# STM32F072B.net
KiCad netlist of a schematic drawn in Altium Designer
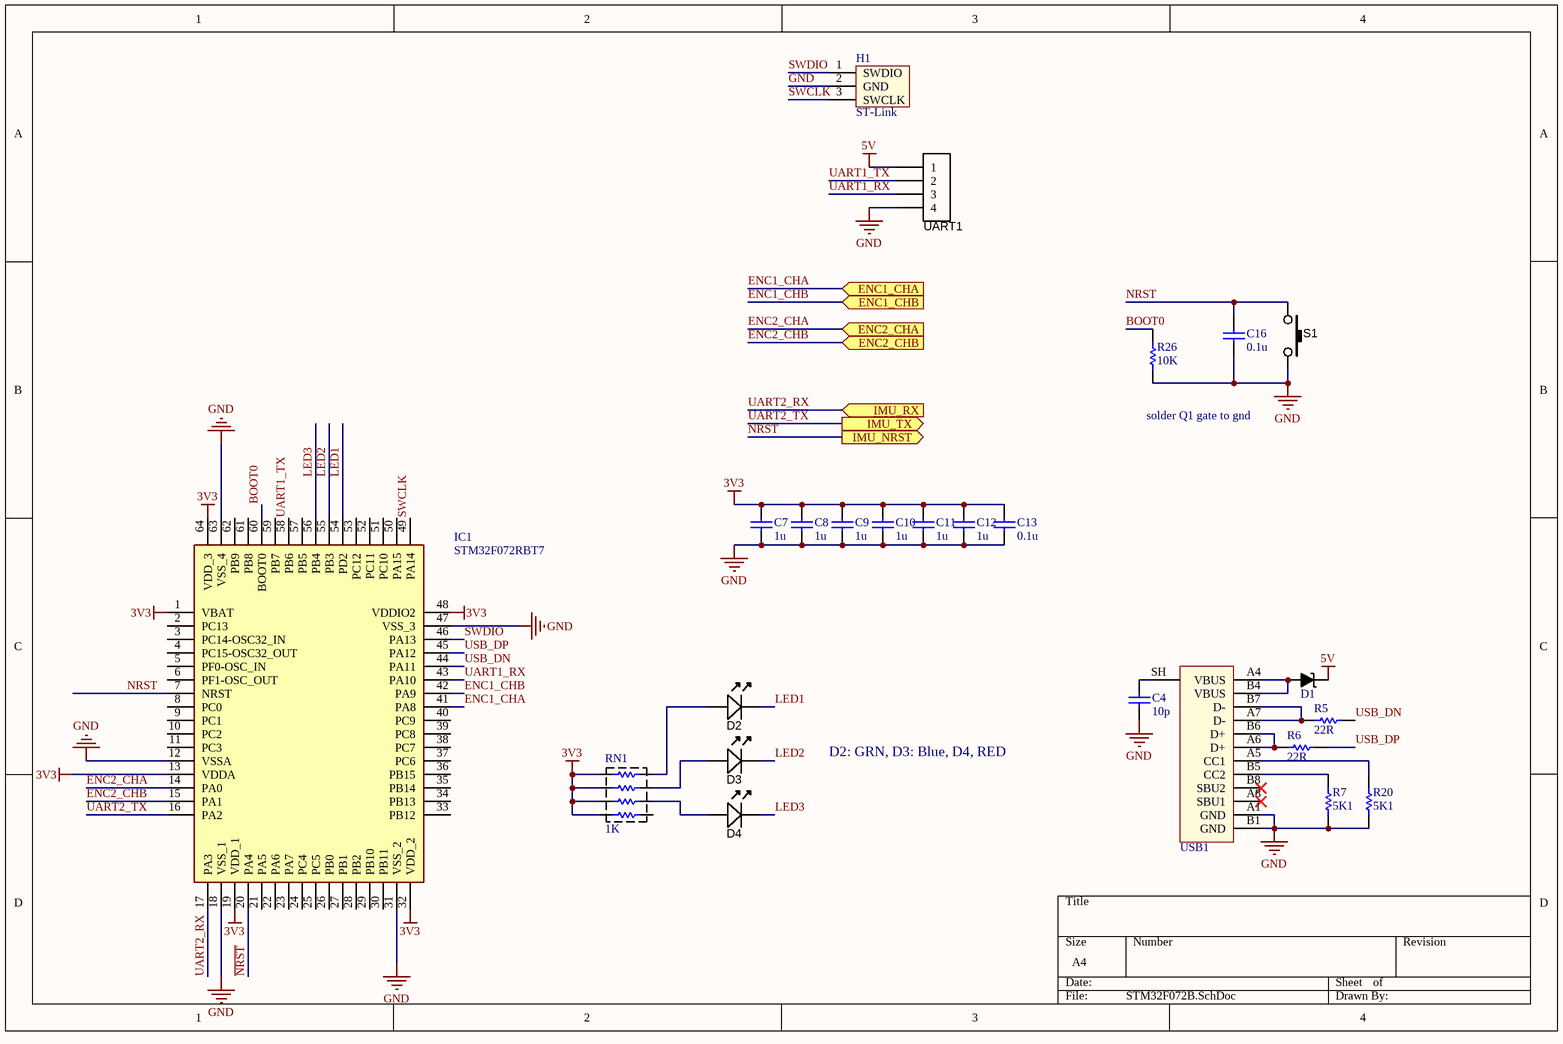
[diagram p0: STM32F072B.SchDoc]

(export (version "E")
  (design (tool "Eeschema 10.0.6"))
  (components
    (comp (ref "C4")
      (value "10p")
      (footprint "CAPC1608X90N")
      (description "Capacitor")
      (fields (field (name "Comment") "Cap") (field (name "PUBLISHER") "Altium Limited"))
      (libsource (lib "IOBoard_Low") (part "Cap"))
    )
    (comp (ref "C7")
      (value "1u")
      (footprint "CAPC1608X90N")
      (description "Capacitor")
      (fields (field (name "Comment") "Cap") (field (name "PUBLISHER") "Altium Limited"))
      (libsource (lib "IOBoard_Low") (part "Cap"))
    )
    (comp (ref "C8")
      (value "1u")
      (footprint "CAPC1608X90N")
      (description "Capacitor")
      (fields (field (name "Comment") "Cap") (field (name "PUBLISHER") "Altium Limited"))
      (libsource (lib "IOBoard_Low") (part "Cap"))
    )
    (comp (ref "C9")
      (value "1u")
      (footprint "CAPC1608X90N")
      (description "Capacitor")
      (fields (field (name "Comment") "Cap") (field (name "PUBLISHER") "Altium Limited"))
      (libsource (lib "IOBoard_Low") (part "Cap"))
    )
    (comp (ref "C10")
      (value "1u")
      (footprint "CAPC1608X90N")
      (description "Capacitor")
      (fields (field (name "Comment") "Cap") (field (name "PUBLISHER") "Altium Limited"))
      (libsource (lib "IOBoard_Low") (part "Cap"))
    )
    (comp (ref "C11")
      (value "1u")
      (footprint "CAPC1608X90N")
      (description "Capacitor")
      (fields (field (name "Comment") "Cap") (field (name "PUBLISHER") "Altium Limited"))
      (libsource (lib "IOBoard_Low") (part "Cap"))
    )
    (comp (ref "C12")
      (value "1u")
      (footprint "CAPC1608X90N")
      (description "Capacitor")
      (fields (field (name "Comment") "Cap") (field (name "PUBLISHER") "Altium Limited"))
      (libsource (lib "IOBoard_Low") (part "Cap"))
    )
    (comp (ref "C13")
      (value "0.1u")
      (footprint "CAPC1608X90N")
      (description "Capacitor")
      (fields (field (name "Comment") "Cap") (field (name "PUBLISHER") "Altium Limited"))
      (libsource (lib "IOBoard_Low") (part "Cap"))
    )
    (comp (ref "C16")
      (value "0.1u")
      (footprint "CAPC1608X90N")
      (description "Capacitor")
      (fields (field (name "Comment") "Cap") (field (name "PUBLISHER") "Altium Limited"))
      (libsource (lib "IOBoard_Low") (part "Cap"))
    )
    (comp (ref "D1")
      (value "diode")
      (footprint "DIODE_3216_70N")
      (description "40V 2A")
      (libsource (lib "IOBoard_Low") (part "SD1206S040S2R0"))
    )
    (comp (ref "D2")
      (value "LED_Green_GullWing")
      (footprint "LED-0805-A")
      (description "LED Gull-wing SMD High-intensity Green 450mcd 574nm")
      (libsource (lib "IOBoard") (part "LED_Green_GullWing"))
    )
    (comp (ref "D3")
      (value "LED_Green_GullWing")
      (footprint "LED-0805-A")
      (description "LED Gull-wing SMD High-intensity Green 450mcd 574nm")
      (libsource (lib "IOBoard") (part "LED_Green_GullWing"))
    )
    (comp (ref "D4")
      (value "LED_Green_GullWing")
      (footprint "LED-0805-A")
      (description "LED Gull-wing SMD High-intensity Green 450mcd 574nm")
      (libsource (lib "IOBoard") (part "LED_Green_GullWing"))
    )
    (comp (ref "H1")
      (value "ST-Link")
      (footprint "ST-Link")
      (description "ST-Link header with silkscreen")
      (libsource (lib "IOBoard") (part "ST-Link"))
    )
    (comp (ref "IC1")
      (value "STM32F072RBT7")
      (footprint "SamacSys:QFP50P1200X1200X160-64N")
      (description "Integrated Circuit")
      (fields (field (name "MOUSER PART NUMBER") "511-STM32F072RBT7"))
      (libsource (lib "*") (part "STM32F072RBT7"))
    )
    (comp (ref "R5")
      (value "22R")
      (footprint "RESC1608X55N")
      (description "Resistor")
      (fields (field (name "Comment") "Res1") (field (name "PUBLISHER") "Altium Limited"))
      (libsource (lib "IOBoard_Low") (part "Res1"))
    )
    (comp (ref "R6")
      (value "22R")
      (footprint "RESC1608X55N")
      (description "Resistor")
      (fields (field (name "Comment") "Res1") (field (name "PUBLISHER") "Altium Limited"))
      (libsource (lib "IOBoard_Low") (part "Res1"))
    )
    (comp (ref "R7")
      (value "5K1")
      (footprint "RESC1608X55N")
      (description "Resistor")
      (fields (field (name "Comment") "Res1") (field (name "PUBLISHER") "Altium Limited"))
      (libsource (lib "IOBoard_Low") (part "Res1"))
    )
    (comp (ref "R20")
      (value "5K1")
      (footprint "RESC1608X55N")
      (description "Resistor")
      (fields (field (name "Comment") "Res1") (field (name "PUBLISHER") "Altium Limited"))
      (libsource (lib "IOBoard_Low") (part "Res1"))
    )
    (comp (ref "R26")
      (value "10K")
      (footprint "RESC1608X55N")
      (description "Resistor")
      (fields (field (name "Comment") "Res1") (field (name "PUBLISHER") "Altium Limited"))
      (libsource (lib "IOBoard_Low") (part "Res1"))
    )
    (comp (ref "RN1")
      (value "1K")
      (footprint "RESCAXS50P160X320X70-8N")
      (fields (field (name "Comment") "resistor network"))
      (libsource (lib "IOBoard") (part "RES_NET"))
    )
    (comp (ref "S1")
      (value "SW_THT_PB_4.3mm")
      (footprint "TACT_SWT-SMD-4.4")
      (description "Switch, tact, 4.3mm stem")
      (libsource (lib "IOBoard") (part "SW_THT_PB_4.3mm"))
    )
    (comp (ref "UART1")
      (value "Programmer")
      (footprint "HDR1X4_2.54MMP")
      (description "Header 4-pin")
      (libsource (lib "IOBoard") (part "Header4P"))
    )
    (comp (ref "USB1")
      (value "USB type C connector")
      (footprint "TYPE-C-31-M-12")
      (libsource (lib "IOBoard") (part "USB_Type_C"))
    )
  )
  (nets
    (net (code "1") (name "/BOOT0") (class "Default")
      (node (ref "IC1") (pin "60") (pinfunction "BOOT0_60") (pintype "passive"))
      (node (ref "R26") (pin "2") (pinfunction "2_2") (pintype "passive"))
    )
    (net (code "2") (name "/ENC1_CHA") (class "Default")
      (node (ref "IC1") (pin "41") (pinfunction "PA8_41") (pintype "passive"))
    )
    (net (code "3") (name "/ENC1_CHB") (class "Default")
      (node (ref "IC1") (pin "42") (pinfunction "PA9_42") (pintype "passive"))
    )
    (net (code "4") (name "/ENC2_CHA") (class "Default")
      (node (ref "IC1") (pin "14") (pinfunction "PA0_14") (pintype "passive"))
    )
    (net (code "5") (name "/ENC2_CHB") (class "Default")
      (node (ref "IC1") (pin "15") (pinfunction "PA1_15") (pintype "passive"))
    )
    (net (code "6") (name "/LED1") (class "Default")
      (node (ref "D2") (pin "K") (pinfunction "K_K") (pintype "passive"))
      (node (ref "IC1") (pin "54") (pinfunction "PD2_54") (pintype "passive"))
    )
    (net (code "7") (name "/LED2") (class "Default")
      (node (ref "D3") (pin "K") (pinfunction "K_K") (pintype "passive"))
      (node (ref "IC1") (pin "55") (pinfunction "PB3_55") (pintype "passive"))
    )
    (net (code "8") (name "/LED3") (class "Default")
      (node (ref "D4") (pin "K") (pinfunction "K_K") (pintype "passive"))
      (node (ref "IC1") (pin "56") (pinfunction "PB4_56") (pintype "passive"))
    )
    (net (code "9") (name "/NRST") (class "Default")
      (node (ref "C16") (pin "2") (pinfunction "2_2") (pintype "passive"))
      (node (ref "IC1") (pin "7") (pinfunction "NRST_7") (pintype "passive"))
      (node (ref "S1") (pin "1") (pintype "passive"))
    )
    (net (code "10") (name "/SWCLK") (class "Default")
      (node (ref "H1") (pin "3") (pinfunction "SWCLK_3") (pintype "power_in"))
      (node (ref "IC1") (pin "49") (pinfunction "PA14_49") (pintype "passive"))
    )
    (net (code "11") (name "/SWDIO") (class "Default")
      (node (ref "H1") (pin "1") (pinfunction "SWDIO_1") (pintype "power_in"))
      (node (ref "IC1") (pin "46") (pinfunction "PA13_46") (pintype "passive"))
    )
    (net (code "12") (name "/UART1_RX") (class "Default")
      (node (ref "IC1") (pin "43") (pinfunction "PA10_43") (pintype "passive"))
      (node (ref "UART1") (pin "3") (pinfunction "3_3") (pintype "passive"))
    )
    (net (code "13") (name "/UART1_TX") (class "Default")
      (node (ref "IC1") (pin "58") (pinfunction "PB6_58") (pintype "passive"))
      (node (ref "UART1") (pin "2") (pinfunction "2_2") (pintype "passive"))
    )
    (net (code "14") (name "/UART2_RX") (class "Default")
      (node (ref "IC1") (pin "17") (pinfunction "PA3_17") (pintype "passive"))
    )
    (net (code "15") (name "/UART2_TX") (class "Default")
      (node (ref "IC1") (pin "16") (pinfunction "PA2_16") (pintype "passive"))
    )
    (net (code "16") (name "/USB_DN") (class "Default")
      (node (ref "IC1") (pin "44") (pinfunction "PA11_44") (pintype "passive"))
      (node (ref "R5") (pin "2") (pinfunction "2_2") (pintype "passive"))
    )
    (net (code "17") (name "/USB_DP") (class "Default")
      (node (ref "IC1") (pin "45") (pinfunction "PA12_45") (pintype "passive"))
      (node (ref "R6") (pin "2") (pinfunction "2_2") (pintype "passive"))
    )
    (net (code "18") (name "/~{NRST}") (class "Default")
      (node (ref "IC1") (pin "20") (pinfunction "PA4_20") (pintype "passive"))
    )
    (net (code "19") (name "3V3") (class "Default")
      (node (ref "C10") (pin "2") (pinfunction "2_2") (pintype "passive"))
      (node (ref "C11") (pin "2") (pinfunction "2_2") (pintype "passive"))
      (node (ref "C12") (pin "2") (pinfunction "2_2") (pintype "passive"))
      (node (ref "C13") (pin "2") (pinfunction "2_2") (pintype "passive"))
      (node (ref "C7") (pin "2") (pinfunction "2_2") (pintype "passive"))
      (node (ref "C8") (pin "2") (pinfunction "2_2") (pintype "passive"))
      (node (ref "C9") (pin "2") (pinfunction "2_2") (pintype "passive"))
      (node (ref "IC1") (pin "1") (pinfunction "VBAT_1") (pintype "passive"))
      (node (ref "IC1") (pin "13") (pinfunction "VDDA_13") (pintype "passive"))
      (node (ref "IC1") (pin "19") (pinfunction "VDD_1_19") (pintype "passive"))
      (node (ref "IC1") (pin "32") (pinfunction "VDD_2_32") (pintype "passive"))
      (node (ref "IC1") (pin "48") (pinfunction "VDDIO2_48") (pintype "passive"))
      (node (ref "IC1") (pin "64") (pinfunction "VDD_3_64") (pintype "passive"))
      (node (ref "RN1") (pin "1") (pinfunction "1_1") (pintype "power_in"))
      (node (ref "RN1") (pin "2") (pinfunction "2_2") (pintype "power_in"))
      (node (ref "RN1") (pin "3") (pinfunction "3_3") (pintype "power_in"))
      (node (ref "RN1") (pin "4") (pinfunction "4_4") (pintype "power_in"))
    )
    (net (code "20") (name "5V") (class "Default")
      (node (ref "D1") (pin "K") (pinfunction "Cathode_K") (pintype "passive"))
      (node (ref "UART1") (pin "1") (pinfunction "1_1") (pintype "passive"))
    )
    (net (code "21") (name "GND") (class "Default")
      (node (ref "C10") (pin "1") (pinfunction "1_1") (pintype "passive"))
      (node (ref "C11") (pin "1") (pinfunction "1_1") (pintype "passive"))
      (node (ref "C12") (pin "1") (pinfunction "1_1") (pintype "passive"))
      (node (ref "C13") (pin "1") (pinfunction "1_1") (pintype "passive"))
      (node (ref "C16") (pin "1") (pinfunction "1_1") (pintype "passive"))
      (node (ref "C4") (pin "1") (pinfunction "1_1") (pintype "passive"))
      (node (ref "C7") (pin "1") (pinfunction "1_1") (pintype "passive"))
      (node (ref "C8") (pin "1") (pinfunction "1_1") (pintype "passive"))
      (node (ref "C9") (pin "1") (pinfunction "1_1") (pintype "passive"))
      (node (ref "H1") (pin "2") (pinfunction "GND_2") (pintype "power_in"))
      (node (ref "IC1") (pin "12") (pinfunction "VSSA_12") (pintype "passive"))
      (node (ref "IC1") (pin "18") (pinfunction "VSS_1_18") (pintype "passive"))
      (node (ref "IC1") (pin "31") (pinfunction "VSS_2_31") (pintype "passive"))
      (node (ref "IC1") (pin "47") (pinfunction "VSS_3_47") (pintype "passive"))
      (node (ref "IC1") (pin "63") (pinfunction "VSS_4_63") (pintype "passive"))
      (node (ref "R20") (pin "1") (pinfunction "1_1") (pintype "passive"))
      (node (ref "R26") (pin "1") (pinfunction "1_1") (pintype "passive"))
      (node (ref "R7") (pin "1") (pinfunction "1_1") (pintype "passive"))
      (node (ref "S1") (pin "2") (pintype "passive"))
      (node (ref "UART1") (pin "4") (pinfunction "4_4") (pintype "passive"))
      (node (ref "USB1") (pin "A1") (pinfunction "GND_A1") (pintype "power_in"))
      (node (ref "USB1") (pin "B1") (pinfunction "GND_B1") (pintype "power_in"))
    )
    (net (code "22") (name "Net-(C4-Pad2)") (class "Default")
      (node (ref "C4") (pin "2") (pinfunction "2_2") (pintype "passive"))
      (node (ref "USB1") (pin "SH") (pinfunction "SH_SH") (pintype "power_in"))
    )
    (net (code "23") (name "Net-(D1-Anode)") (class "Default")
      (node (ref "D1") (pin "A") (pinfunction "Anode_A") (pintype "passive"))
      (node (ref "USB1") (pin "A4") (pinfunction "VBUS_A4") (pintype "power_in"))
      (node (ref "USB1") (pin "B4") (pinfunction "VBUS_B4") (pintype "power_in"))
    )
    (net (code "24") (name "Net-(D2-PadA)") (class "Default")
      (node (ref "D2") (pin "A") (pinfunction "A_A") (pintype "passive"))
      (node (ref "RN1") (pin "8") (pinfunction "8_8") (pintype "power_in"))
    )
    (net (code "25") (name "Net-(D3-PadA)") (class "Default")
      (node (ref "D3") (pin "A") (pinfunction "A_A") (pintype "passive"))
      (node (ref "RN1") (pin "7") (pinfunction "7_7") (pintype "power_in"))
    )
    (net (code "26") (name "Net-(D4-PadA)") (class "Default")
      (node (ref "D4") (pin "A") (pinfunction "A_A") (pintype "passive"))
      (node (ref "RN1") (pin "6") (pinfunction "6_6") (pintype "power_in"))
    )
    (net (code "27") (name "Net-(R5-Pad1)") (class "Default")
      (node (ref "R5") (pin "1") (pinfunction "1_1") (pintype "passive"))
      (node (ref "USB1") (pin "A7") (pinfunction "D-_A7") (pintype "power_in"))
      (node (ref "USB1") (pin "B7") (pinfunction "D-_B7") (pintype "power_in"))
    )
    (net (code "28") (name "Net-(R6-Pad1)") (class "Default")
      (node (ref "R6") (pin "1") (pinfunction "1_1") (pintype "passive"))
      (node (ref "USB1") (pin "A6") (pinfunction "D+_A6") (pintype "power_in"))
      (node (ref "USB1") (pin "B6") (pinfunction "D+_B6") (pintype "power_in"))
    )
    (net (code "29") (name "Net-(USB1-CC1)") (class "Default")
      (node (ref "R20") (pin "2") (pinfunction "2_2") (pintype "passive"))
      (node (ref "USB1") (pin "A5") (pinfunction "CC1_A5") (pintype "power_in"))
    )
    (net (code "30") (name "Net-(USB1-CC2)") (class "Default")
      (node (ref "R7") (pin "2") (pinfunction "2_2") (pintype "passive"))
      (node (ref "USB1") (pin "B5") (pinfunction "CC2_B5") (pintype "power_in"))
    )
    (net (code "31") (name "unconnected-(IC1-PA5-Pad21)") (class "Default")
      (node (ref "IC1") (pin "21") (pinfunction "PA5_21") (pintype "passive"))
    )
    (net (code "32") (name "unconnected-(IC1-PA6-Pad22)") (class "Default")
      (node (ref "IC1") (pin "22") (pinfunction "PA6_22") (pintype "passive"))
    )
    (net (code "33") (name "unconnected-(IC1-PA7-Pad23)") (class "Default")
      (node (ref "IC1") (pin "23") (pinfunction "PA7_23") (pintype "passive"))
    )
    (net (code "34") (name "unconnected-(IC1-PA15-Pad50)") (class "Default")
      (node (ref "IC1") (pin "50") (pinfunction "PA15_50") (pintype "passive"))
    )
    (net (code "35") (name "unconnected-(IC1-PB0-Pad26)") (class "Default")
      (node (ref "IC1") (pin "26") (pinfunction "PB0_26") (pintype "passive"))
    )
    (net (code "36") (name "unconnected-(IC1-PB1-Pad27)") (class "Default")
      (node (ref "IC1") (pin "27") (pinfunction "PB1_27") (pintype "passive"))
    )
    (net (code "37") (name "unconnected-(IC1-PB2-Pad28)") (class "Default")
      (node (ref "IC1") (pin "28") (pinfunction "PB2_28") (pintype "passive"))
    )
    (net (code "38") (name "unconnected-(IC1-PB5-Pad57)") (class "Default")
      (node (ref "IC1") (pin "57") (pinfunction "PB5_57") (pintype "passive"))
    )
    (net (code "39") (name "unconnected-(IC1-PB7-Pad59)") (class "Default")
      (node (ref "IC1") (pin "59") (pinfunction "PB7_59") (pintype "passive"))
    )
    (net (code "40") (name "unconnected-(IC1-PB8-Pad61)") (class "Default")
      (node (ref "IC1") (pin "61") (pinfunction "PB8_61") (pintype "passive"))
    )
    (net (code "41") (name "unconnected-(IC1-PB9-Pad62)") (class "Default")
      (node (ref "IC1") (pin "62") (pinfunction "PB9_62") (pintype "passive"))
    )
    (net (code "42") (name "unconnected-(IC1-PB10-Pad29)") (class "Default")
      (node (ref "IC1") (pin "29") (pinfunction "PB10_29") (pintype "passive"))
    )
    (net (code "43") (name "unconnected-(IC1-PB11-Pad30)") (class "Default")
      (node (ref "IC1") (pin "30") (pinfunction "PB11_30") (pintype "passive"))
    )
    (net (code "44") (name "unconnected-(IC1-PB12-Pad33)") (class "Default")
      (node (ref "IC1") (pin "33") (pinfunction "PB12_33") (pintype "passive"))
    )
    (net (code "45") (name "unconnected-(IC1-PB13-Pad34)") (class "Default")
      (node (ref "IC1") (pin "34") (pinfunction "PB13_34") (pintype "passive"))
    )
    (net (code "46") (name "unconnected-(IC1-PB14-Pad35)") (class "Default")
      (node (ref "IC1") (pin "35") (pinfunction "PB14_35") (pintype "passive"))
    )
    (net (code "47") (name "unconnected-(IC1-PB15-Pad36)") (class "Default")
      (node (ref "IC1") (pin "36") (pinfunction "PB15_36") (pintype "passive"))
    )
    (net (code "48") (name "unconnected-(IC1-PC0-Pad8)") (class "Default")
      (node (ref "IC1") (pin "8") (pinfunction "PC0_8") (pintype "passive"))
    )
    (net (code "49") (name "unconnected-(IC1-PC1-Pad9)") (class "Default")
      (node (ref "IC1") (pin "9") (pinfunction "PC1_9") (pintype "passive"))
    )
    (net (code "50") (name "unconnected-(IC1-PC2-Pad10)") (class "Default")
      (node (ref "IC1") (pin "10") (pinfunction "PC2_10") (pintype "passive"))
    )
    (net (code "51") (name "unconnected-(IC1-PC3-Pad11)") (class "Default")
      (node (ref "IC1") (pin "11") (pinfunction "PC3_11") (pintype "passive"))
    )
    (net (code "52") (name "unconnected-(IC1-PC4-Pad24)") (class "Default")
      (node (ref "IC1") (pin "24") (pinfunction "PC4_24") (pintype "passive"))
    )
    (net (code "53") (name "unconnected-(IC1-PC5-Pad25)") (class "Default")
      (node (ref "IC1") (pin "25") (pinfunction "PC5_25") (pintype "passive"))
    )
    (net (code "54") (name "unconnected-(IC1-PC6-Pad37)") (class "Default")
      (node (ref "IC1") (pin "37") (pinfunction "PC6_37") (pintype "passive"))
    )
    (net (code "55") (name "unconnected-(IC1-PC7-Pad38)") (class "Default")
      (node (ref "IC1") (pin "38") (pinfunction "PC7_38") (pintype "passive"))
    )
    (net (code "56") (name "unconnected-(IC1-PC8-Pad39)") (class "Default")
      (node (ref "IC1") (pin "39") (pinfunction "PC8_39") (pintype "passive"))
    )
    (net (code "57") (name "unconnected-(IC1-PC9-Pad40)") (class "Default")
      (node (ref "IC1") (pin "40") (pinfunction "PC9_40") (pintype "passive"))
    )
    (net (code "58") (name "unconnected-(IC1-PC10-Pad51)") (class "Default")
      (node (ref "IC1") (pin "51") (pinfunction "PC10_51") (pintype "passive"))
    )
    (net (code "59") (name "unconnected-(IC1-PC11-Pad52)") (class "Default")
      (node (ref "IC1") (pin "52") (pinfunction "PC11_52") (pintype "passive"))
    )
    (net (code "60") (name "unconnected-(IC1-PC12-Pad53)") (class "Default")
      (node (ref "IC1") (pin "53") (pinfunction "PC12_53") (pintype "passive"))
    )
    (net (code "61") (name "unconnected-(IC1-PC13-Pad2)") (class "Default")
      (node (ref "IC1") (pin "2") (pinfunction "PC13_2") (pintype "passive"))
    )
    (net (code "62") (name "unconnected-(IC1-PC14-OSC32_IN-Pad3)") (class "Default")
      (node (ref "IC1") (pin "3") (pinfunction "PC14-OSC32_IN_3") (pintype "passive"))
    )
    (net (code "63") (name "unconnected-(IC1-PC15-OSC32_OUT-Pad4)") (class "Default")
      (node (ref "IC1") (pin "4") (pinfunction "PC15-OSC32_OUT_4") (pintype "passive"))
    )
    (net (code "64") (name "unconnected-(IC1-PF0-OSC_IN-Pad5)") (class "Default")
      (node (ref "IC1") (pin "5") (pinfunction "PF0-OSC_IN_5") (pintype "passive"))
    )
    (net (code "65") (name "unconnected-(IC1-PF1-OSC_OUT-Pad6)") (class "Default")
      (node (ref "IC1") (pin "6") (pinfunction "PF1-OSC_OUT_6") (pintype "passive"))
    )
    (net (code "66") (name "unconnected-(RN1-Pad5)") (class "Default")
      (node (ref "RN1") (pin "5") (pinfunction "5_5") (pintype "power_in"))
    )
    (net (code "67") (name "unconnected-(USB1-SBU1-PadA8)") (class "Default")
      (node (ref "USB1") (pin "A8") (pinfunction "SBU1_A8") (pintype "power_in+no_connect"))
    )
    (net (code "68") (name "unconnected-(USB1-SBU2-PadB8)") (class "Default")
      (node (ref "USB1") (pin "B8") (pinfunction "SBU2_B8") (pintype "power_in+no_connect"))
    )
  )
)
